# FPGA_ADC_N.net
KiCad netlist of a schematic drawn in Altium Designer
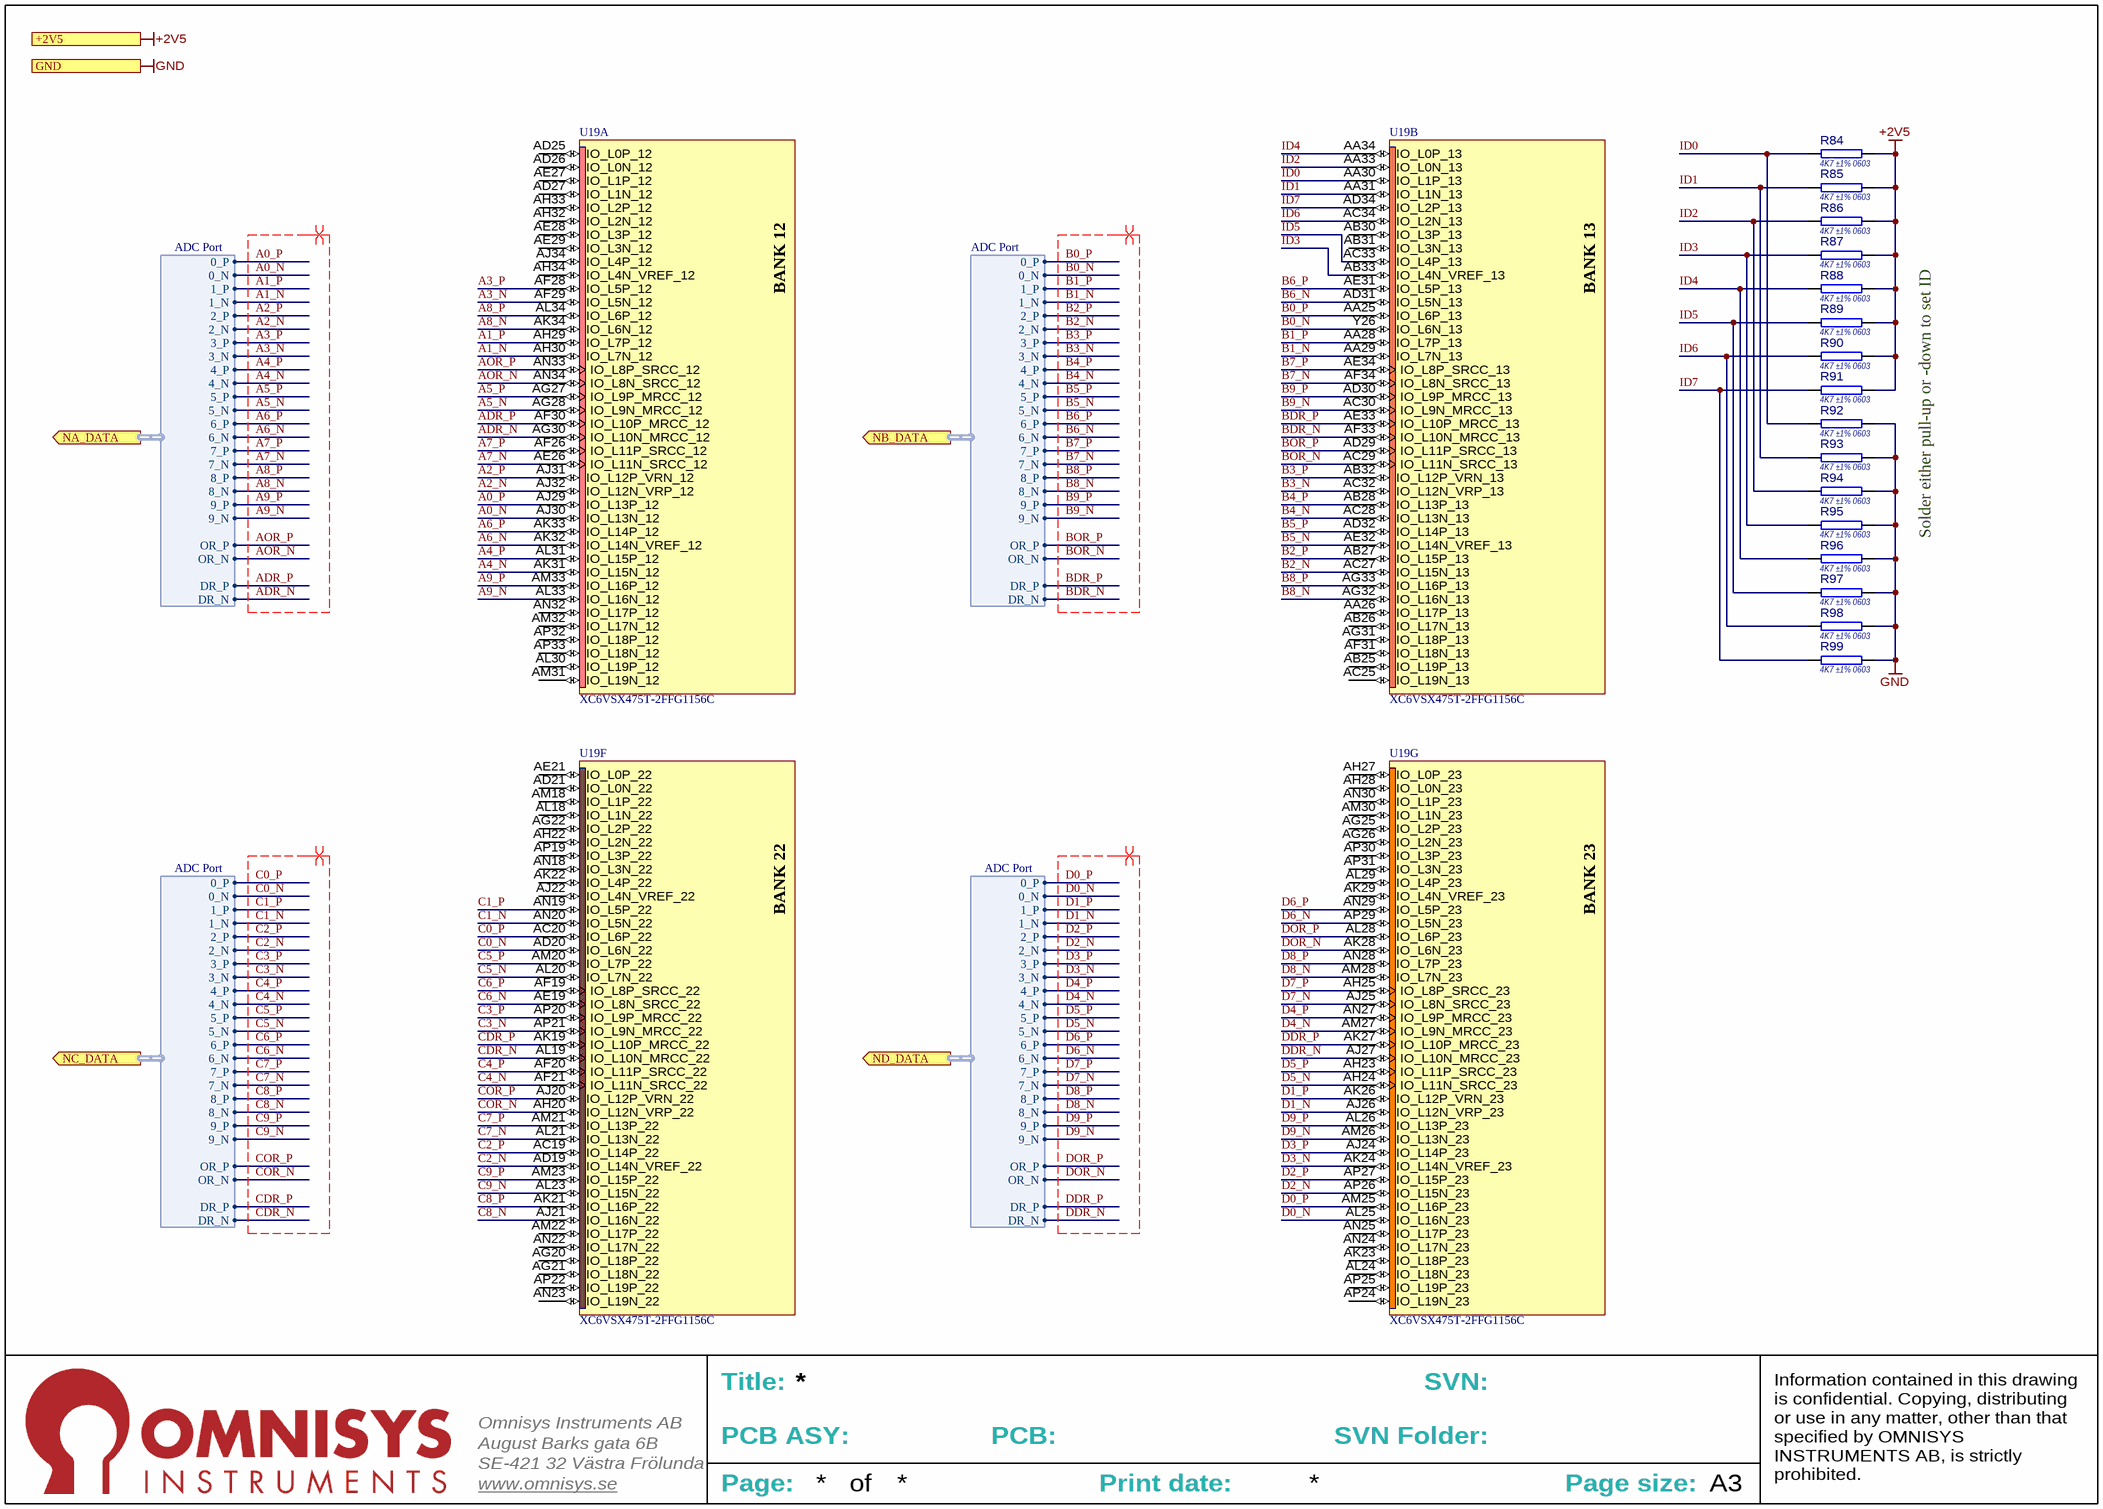
[diagram p0: FPGA_ADC_N.SchDoc]

(export (version "E")
  (design (tool "Eeschema 10.0.6"))
  (components
    (comp (ref "R84")
      (value "4K7 ±1% 0603")
      (footprint "RESC1608N")
      (description "4K7 ±1% ±100 ppm/˚C 0.10W 75V 0603 (1608 metric)")
      (fields (field (name "POWER") "100mW") (field (name "TOLERANCE") "1%"))
      (libsource (lib "Omnisys Vault") (part "RES-2PIN"))
    )
    (comp (ref "R85")
      (value "4K7 ±1% 0603")
      (footprint "RESC1608N")
      (description "4K7 ±1% ±100 ppm/˚C 0.10W 75V 0603 (1608 metric)")
      (fields (field (name "POWER") "100mW") (field (name "TOLERANCE") "1%"))
      (libsource (lib "Omnisys Vault") (part "RES-2PIN"))
    )
    (comp (ref "R86")
      (value "4K7 ±1% 0603")
      (footprint "RESC1608N")
      (description "4K7 ±1% ±100 ppm/˚C 0.10W 75V 0603 (1608 metric)")
      (fields (field (name "POWER") "100mW") (field (name "TOLERANCE") "1%"))
      (libsource (lib "Omnisys Vault") (part "RES-2PIN"))
    )
    (comp (ref "R87")
      (value "4K7 ±1% 0603")
      (footprint "RESC1608N")
      (description "4K7 ±1% ±100 ppm/˚C 0.10W 75V 0603 (1608 metric)")
      (fields (field (name "POWER") "100mW") (field (name "TOLERANCE") "1%"))
      (libsource (lib "Omnisys Vault") (part "RES-2PIN"))
    )
    (comp (ref "R88")
      (value "4K7 ±1% 0603")
      (footprint "RESC1608N")
      (description "4K7 ±1% ±100 ppm/˚C 0.10W 75V 0603 (1608 metric)")
      (fields (field (name "POWER") "100mW") (field (name "TOLERANCE") "1%"))
      (libsource (lib "Omnisys Vault") (part "RES-2PIN"))
    )
    (comp (ref "R89")
      (value "4K7 ±1% 0603")
      (footprint "RESC1608N")
      (description "4K7 ±1% ±100 ppm/˚C 0.10W 75V 0603 (1608 metric)")
      (fields (field (name "POWER") "100mW") (field (name "TOLERANCE") "1%"))
      (libsource (lib "Omnisys Vault") (part "RES-2PIN"))
    )
    (comp (ref "R90")
      (value "4K7 ±1% 0603")
      (footprint "RESC1608N")
      (description "4K7 ±1% ±100 ppm/˚C 0.10W 75V 0603 (1608 metric)")
      (fields (field (name "POWER") "100mW") (field (name "TOLERANCE") "1%"))
      (libsource (lib "Omnisys Vault") (part "RES-2PIN"))
    )
    (comp (ref "R91")
      (value "4K7 ±1% 0603")
      (footprint "RESC1608N")
      (description "4K7 ±1% ±100 ppm/˚C 0.10W 75V 0603 (1608 metric)")
      (fields (field (name "POWER") "100mW") (field (name "TOLERANCE") "1%"))
      (libsource (lib "Omnisys Vault") (part "RES-2PIN"))
    )
    (comp (ref "R92")
      (value "4K7 ±1% 0603")
      (footprint "RESC1608N")
      (description "4K7 ±1% ±100 ppm/˚C 0.10W 75V 0603 (1608 metric)")
      (fields (field (name "POWER") "100mW") (field (name "TOLERANCE") "1%"))
      (libsource (lib "Omnisys Vault") (part "RES-2PIN"))
    )
    (comp (ref "R93")
      (value "4K7 ±1% 0603")
      (footprint "RESC1608N")
      (description "4K7 ±1% ±100 ppm/˚C 0.10W 75V 0603 (1608 metric)")
      (fields (field (name "POWER") "100mW") (field (name "TOLERANCE") "1%"))
      (libsource (lib "Omnisys Vault") (part "RES-2PIN"))
    )
    (comp (ref "R94")
      (value "4K7 ±1% 0603")
      (footprint "RESC1608N")
      (description "4K7 ±1% ±100 ppm/˚C 0.10W 75V 0603 (1608 metric)")
      (fields (field (name "POWER") "100mW") (field (name "TOLERANCE") "1%"))
      (libsource (lib "Omnisys Vault") (part "RES-2PIN"))
    )
    (comp (ref "R95")
      (value "4K7 ±1% 0603")
      (footprint "RESC1608N")
      (description "4K7 ±1% ±100 ppm/˚C 0.10W 75V 0603 (1608 metric)")
      (fields (field (name "POWER") "100mW") (field (name "TOLERANCE") "1%"))
      (libsource (lib "Omnisys Vault") (part "RES-2PIN"))
    )
    (comp (ref "R96")
      (value "4K7 ±1% 0603")
      (footprint "RESC1608N")
      (description "4K7 ±1% ±100 ppm/˚C 0.10W 75V 0603 (1608 metric)")
      (fields (field (name "POWER") "100mW") (field (name "TOLERANCE") "1%"))
      (libsource (lib "Omnisys Vault") (part "RES-2PIN"))
    )
    (comp (ref "R97")
      (value "4K7 ±1% 0603")
      (footprint "RESC1608N")
      (description "4K7 ±1% ±100 ppm/˚C 0.10W 75V 0603 (1608 metric)")
      (fields (field (name "POWER") "100mW") (field (name "TOLERANCE") "1%"))
      (libsource (lib "Omnisys Vault") (part "RES-2PIN"))
    )
    (comp (ref "R98")
      (value "4K7 ±1% 0603")
      (footprint "RESC1608N")
      (description "4K7 ±1% ±100 ppm/˚C 0.10W 75V 0603 (1608 metric)")
      (fields (field (name "POWER") "100mW") (field (name "TOLERANCE") "1%"))
      (libsource (lib "Omnisys Vault") (part "RES-2PIN"))
    )
    (comp (ref "R99")
      (value "4K7 ±1% 0603")
      (footprint "RESC1608N")
      (description "4K7 ±1% ±100 ppm/˚C 0.10W 75V 0603 (1608 metric)")
      (fields (field (name "POWER") "100mW") (field (name "TOLERANCE") "1%"))
      (libsource (lib "Omnisys Vault") (part "RES-2PIN"))
    )
    (comp (ref "U19")
      (value "XC6VSX475T-2FFG1156C")
      (footprint "FFG1156")
      (libsource (lib "Altium Content Vault") (part "FPGA-XVR6-XC6VXXXXXT-GA1156"))
    )
  )
  (nets
    (net (code "3") (name "+2V5") (class "Default")
      (node (ref "R84") (pin "1") (pinfunction "1_1") (pintype "passive"))
      (node (ref "R85") (pin "1") (pinfunction "1_1") (pintype "passive"))
      (node (ref "R86") (pin "1") (pinfunction "1_1") (pintype "passive"))
      (node (ref "R87") (pin "1") (pinfunction "1_1") (pintype "passive"))
      (node (ref "R88") (pin "1") (pinfunction "1_1") (pintype "passive"))
      (node (ref "R89") (pin "1") (pinfunction "1_1") (pintype "passive"))
      (node (ref "R90") (pin "1") (pinfunction "1_1") (pintype "passive"))
      (node (ref "R91") (pin "1") (pinfunction "1_1") (pintype "passive"))
    )
    (net (code "4") (name "/A0_N") (class "Default")
      (node (ref "U19") (pin "AJ30") (pinfunction "IO_L13N_12_AJ30") (pintype "bidirectional"))
    )
    (net (code "5") (name "/A0_P") (class "Default")
      (node (ref "U19") (pin "AJ29") (pinfunction "IO_L13P_12_AJ29") (pintype "bidirectional"))
    )
    (net (code "6") (name "/A1_N") (class "Default")
      (node (ref "U19") (pin "AH30") (pinfunction "IO_L7N_12_AH30") (pintype "bidirectional"))
    )
    (net (code "7") (name "/A1_P") (class "Default")
      (node (ref "U19") (pin "AH29") (pinfunction "IO_L7P_12_AH29") (pintype "bidirectional"))
    )
    (net (code "8") (name "/A2_N") (class "Default")
      (node (ref "U19") (pin "AJ32") (pinfunction "IO_L12N_VRP_12_AJ32") (pintype "bidirectional"))
    )
    (net (code "9") (name "/A2_P") (class "Default")
      (node (ref "U19") (pin "AJ31") (pinfunction "IO_L12P_VRN_12_AJ31") (pintype "bidirectional"))
    )
    (net (code "10") (name "/A3_N") (class "Default")
      (node (ref "U19") (pin "AF29") (pinfunction "IO_L5N_12_AF29") (pintype "bidirectional"))
    )
    (net (code "11") (name "/A3_P") (class "Default")
      (node (ref "U19") (pin "AF28") (pinfunction "IO_L5P_12_AF28") (pintype "bidirectional"))
    )
    (net (code "12") (name "/A4_N") (class "Default")
      (node (ref "U19") (pin "AK31") (pinfunction "IO_L15N_12_AK31") (pintype "bidirectional"))
    )
    (net (code "13") (name "/A4_P") (class "Default")
      (node (ref "U19") (pin "AL31") (pinfunction "IO_L15P_12_AL31") (pintype "bidirectional"))
    )
    (net (code "14") (name "/A5_N") (class "Default")
      (node (ref "U19") (pin "AG28") (pinfunction "IO_L9N_MRCC_12_AG28") (pintype "bidirectional"))
    )
    (net (code "15") (name "/A5_P") (class "Default")
      (node (ref "U19") (pin "AG27") (pinfunction "IO_L9P_MRCC_12_AG27") (pintype "bidirectional"))
    )
    (net (code "16") (name "/A6_N") (class "Default")
      (node (ref "U19") (pin "AK32") (pinfunction "IO_L14N_VREF_12_AK32") (pintype "bidirectional"))
    )
    (net (code "17") (name "/A6_P") (class "Default")
      (node (ref "U19") (pin "AK33") (pinfunction "IO_L14P_12_AK33") (pintype "bidirectional"))
    )
    (net (code "18") (name "/A7_N") (class "Default")
      (node (ref "U19") (pin "AE26") (pinfunction "IO_L11N_SRCC_12_AE26") (pintype "bidirectional"))
    )
    (net (code "19") (name "/A7_P") (class "Default")
      (node (ref "U19") (pin "AF26") (pinfunction "IO_L11P_SRCC_12_AF26") (pintype "bidirectional"))
    )
    (net (code "20") (name "/A8_N") (class "Default")
      (node (ref "U19") (pin "AK34") (pinfunction "IO_L6N_12_AK34") (pintype "bidirectional"))
    )
    (net (code "21") (name "/A8_P") (class "Default")
      (node (ref "U19") (pin "AL34") (pinfunction "IO_L6P_12_AL34") (pintype "bidirectional"))
    )
    (net (code "22") (name "/A9_N") (class "Default")
      (node (ref "U19") (pin "AL33") (pinfunction "IO_L16N_12_AL33") (pintype "bidirectional"))
    )
    (net (code "23") (name "/A9_P") (class "Default")
      (node (ref "U19") (pin "AM33") (pinfunction "IO_L16P_12_AM33") (pintype "bidirectional"))
    )
    (net (code "24") (name "/ADR_N") (class "Default")
      (node (ref "U19") (pin "AG30") (pinfunction "IO_L10N_MRCC_12_AG30") (pintype "bidirectional"))
    )
    (net (code "25") (name "/ADR_P") (class "Default")
      (node (ref "U19") (pin "AF30") (pinfunction "IO_L10P_MRCC_12_AF30") (pintype "bidirectional"))
    )
    (net (code "26") (name "/AOR_N") (class "Default")
      (node (ref "U19") (pin "AN34") (pinfunction "IO_L8N_SRCC_12_AN34") (pintype "bidirectional"))
    )
    (net (code "27") (name "/AOR_P") (class "Default")
      (node (ref "U19") (pin "AN33") (pinfunction "IO_L8P_SRCC_12_AN33") (pintype "bidirectional"))
    )
    (net (code "28") (name "/B0_N") (class "Default")
      (node (ref "U19") (pin "Y26") (pinfunction "IO_L6N_13_Y26") (pintype "bidirectional"))
    )
    (net (code "29") (name "/B0_P") (class "Default")
      (node (ref "U19") (pin "AA25") (pinfunction "IO_L6P_13_AA25") (pintype "bidirectional"))
    )
    (net (code "30") (name "/B1_N") (class "Default")
      (node (ref "U19") (pin "AA29") (pinfunction "IO_L7N_13_AA29") (pintype "bidirectional"))
    )
    (net (code "31") (name "/B1_P") (class "Default")
      (node (ref "U19") (pin "AA28") (pinfunction "IO_L7P_13_AA28") (pintype "bidirectional"))
    )
    (net (code "32") (name "/B2_N") (class "Default")
      (node (ref "U19") (pin "AC27") (pinfunction "IO_L15N_13_AC27") (pintype "bidirectional"))
    )
    (net (code "33") (name "/B2_P") (class "Default")
      (node (ref "U19") (pin "AB27") (pinfunction "IO_L15P_13_AB27") (pintype "bidirectional"))
    )
    (net (code "34") (name "/B3_N") (class "Default")
      (node (ref "U19") (pin "AC32") (pinfunction "IO_L12N_VRP_13_AC32") (pintype "bidirectional"))
    )
    (net (code "35") (name "/B3_P") (class "Default")
      (node (ref "U19") (pin "AB32") (pinfunction "IO_L12P_VRN_13_AB32") (pintype "bidirectional"))
    )
    (net (code "36") (name "/B4_N") (class "Default")
      (node (ref "U19") (pin "AC28") (pinfunction "IO_L13N_13_AC28") (pintype "bidirectional"))
    )
    (net (code "37") (name "/B4_P") (class "Default")
      (node (ref "U19") (pin "AB28") (pinfunction "IO_L13P_13_AB28") (pintype "bidirectional"))
    )
    (net (code "38") (name "/B5_N") (class "Default")
      (node (ref "U19") (pin "AE32") (pinfunction "IO_L14N_VREF_13_AE32") (pintype "bidirectional"))
    )
    (net (code "39") (name "/B5_P") (class "Default")
      (node (ref "U19") (pin "AD32") (pinfunction "IO_L14P_13_AD32") (pintype "bidirectional"))
    )
    (net (code "40") (name "/B6_N") (class "Default")
      (node (ref "U19") (pin "AD31") (pinfunction "IO_L5N_13_AD31") (pintype "bidirectional"))
    )
    (net (code "41") (name "/B6_P") (class "Default")
      (node (ref "U19") (pin "AE31") (pinfunction "IO_L5P_13_AE31") (pintype "bidirectional"))
    )
    (net (code "42") (name "/B7_N") (class "Default")
      (node (ref "U19") (pin "AF34") (pinfunction "IO_L8N_SRCC_13_AF34") (pintype "bidirectional"))
    )
    (net (code "43") (name "/B7_P") (class "Default")
      (node (ref "U19") (pin "AE34") (pinfunction "IO_L8P_SRCC_13_AE34") (pintype "bidirectional"))
    )
    (net (code "44") (name "/B8_N") (class "Default")
      (node (ref "U19") (pin "AG32") (pinfunction "IO_L16N_13_AG32") (pintype "bidirectional"))
    )
    (net (code "45") (name "/B8_P") (class "Default")
      (node (ref "U19") (pin "AG33") (pinfunction "IO_L16P_13_AG33") (pintype "bidirectional"))
    )
    (net (code "46") (name "/B9_N") (class "Default")
      (node (ref "U19") (pin "AC30") (pinfunction "IO_L9N_MRCC_13_AC30") (pintype "bidirectional"))
    )
    (net (code "47") (name "/B9_P") (class "Default")
      (node (ref "U19") (pin "AD30") (pinfunction "IO_L9P_MRCC_13_AD30") (pintype "bidirectional"))
    )
    (net (code "48") (name "/BDR_N") (class "Default")
      (node (ref "U19") (pin "AF33") (pinfunction "IO_L10N_MRCC_13_AF33") (pintype "bidirectional"))
    )
    (net (code "49") (name "/BDR_P") (class "Default")
      (node (ref "U19") (pin "AE33") (pinfunction "IO_L10P_MRCC_13_AE33") (pintype "bidirectional"))
    )
    (net (code "50") (name "/BOR_N") (class "Default")
      (node (ref "U19") (pin "AC29") (pinfunction "IO_L11N_SRCC_13_AC29") (pintype "bidirectional"))
    )
    (net (code "51") (name "/BOR_P") (class "Default")
      (node (ref "U19") (pin "AD29") (pinfunction "IO_L11P_SRCC_13_AD29") (pintype "bidirectional"))
    )
    (net (code "52") (name "/C0_N") (class "Default")
      (node (ref "U19") (pin "AD20") (pinfunction "IO_L6N_22_AD20") (pintype "bidirectional"))
    )
    (net (code "53") (name "/C0_P") (class "Default")
      (node (ref "U19") (pin "AC20") (pinfunction "IO_L6P_22_AC20") (pintype "bidirectional"))
    )
    (net (code "54") (name "/C1_N") (class "Default")
      (node (ref "U19") (pin "AN20") (pinfunction "IO_L5N_22_AN20") (pintype "bidirectional"))
    )
    (net (code "55") (name "/C1_P") (class "Default")
      (node (ref "U19") (pin "AN19") (pinfunction "IO_L5P_22_AN19") (pintype "bidirectional"))
    )
    (net (code "56") (name "/C2_N") (class "Default")
      (node (ref "U19") (pin "AD19") (pinfunction "IO_L14N_VREF_22_AD19") (pintype "bidirectional"))
    )
    (net (code "57") (name "/C2_P") (class "Default")
      (node (ref "U19") (pin "AC19") (pinfunction "IO_L14P_22_AC19") (pintype "bidirectional"))
    )
    (net (code "58") (name "/C3_N") (class "Default")
      (node (ref "U19") (pin "AP21") (pinfunction "IO_L9N_MRCC_22_AP21") (pintype "bidirectional"))
    )
    (net (code "59") (name "/C3_P") (class "Default")
      (node (ref "U19") (pin "AP20") (pinfunction "IO_L9P_MRCC_22_AP20") (pintype "bidirectional"))
    )
    (net (code "60") (name "/C4_N") (class "Default")
      (node (ref "U19") (pin "AF21") (pinfunction "IO_L11N_SRCC_22_AF21") (pintype "bidirectional"))
    )
    (net (code "61") (name "/C4_P") (class "Default")
      (node (ref "U19") (pin "AF20") (pinfunction "IO_L11P_SRCC_22_AF20") (pintype "bidirectional"))
    )
    (net (code "62") (name "/C5_N") (class "Default")
      (node (ref "U19") (pin "AL20") (pinfunction "IO_L7N_22_AL20") (pintype "bidirectional"))
    )
    (net (code "63") (name "/C5_P") (class "Default")
      (node (ref "U19") (pin "AM20") (pinfunction "IO_L7P_22_AM20") (pintype "bidirectional"))
    )
    (net (code "64") (name "/C6_N") (class "Default")
      (node (ref "U19") (pin "AE19") (pinfunction "IO_L8N_SRCC_22_AE19") (pintype "bidirectional"))
    )
    (net (code "65") (name "/C6_P") (class "Default")
      (node (ref "U19") (pin "AF19") (pinfunction "IO_L8P_SRCC_22_AF19") (pintype "bidirectional"))
    )
    (net (code "66") (name "/C7_N") (class "Default")
      (node (ref "U19") (pin "AL21") (pinfunction "IO_L13N_22_AL21") (pintype "bidirectional"))
    )
    (net (code "67") (name "/C7_P") (class "Default")
      (node (ref "U19") (pin "AM21") (pinfunction "IO_L13P_22_AM21") (pintype "bidirectional"))
    )
    (net (code "68") (name "/C8_N") (class "Default")
      (node (ref "U19") (pin "AJ21") (pinfunction "IO_L16N_22_AJ21") (pintype "bidirectional"))
    )
    (net (code "69") (name "/C8_P") (class "Default")
      (node (ref "U19") (pin "AK21") (pinfunction "IO_L16P_22_AK21") (pintype "bidirectional"))
    )
    (net (code "70") (name "/C9_N") (class "Default")
      (node (ref "U19") (pin "AL23") (pinfunction "IO_L15N_22_AL23") (pintype "bidirectional"))
    )
    (net (code "71") (name "/C9_P") (class "Default")
      (node (ref "U19") (pin "AM23") (pinfunction "IO_L15P_22_AM23") (pintype "bidirectional"))
    )
    (net (code "72") (name "/CDR_N") (class "Default")
      (node (ref "U19") (pin "AL19") (pinfunction "IO_L10N_MRCC_22_AL19") (pintype "bidirectional"))
    )
    (net (code "73") (name "/CDR_P") (class "Default")
      (node (ref "U19") (pin "AK19") (pinfunction "IO_L10P_MRCC_22_AK19") (pintype "bidirectional"))
    )
    (net (code "74") (name "/COR_N") (class "Default")
      (node (ref "U19") (pin "AH20") (pinfunction "IO_L12N_VRP_22_AH20") (pintype "bidirectional"))
    )
    (net (code "75") (name "/COR_P") (class "Default")
      (node (ref "U19") (pin "AJ20") (pinfunction "IO_L12P_VRN_22_AJ20") (pintype "bidirectional"))
    )
    (net (code "76") (name "/D0_N") (class "Default")
      (node (ref "U19") (pin "AL25") (pinfunction "IO_L16N_23_AL25") (pintype "bidirectional"))
    )
    (net (code "77") (name "/D0_P") (class "Default")
      (node (ref "U19") (pin "AM25") (pinfunction "IO_L16P_23_AM25") (pintype "bidirectional"))
    )
    (net (code "78") (name "/D1_N") (class "Default")
      (node (ref "U19") (pin "AJ26") (pinfunction "IO_L12N_VRP_23_AJ26") (pintype "bidirectional"))
    )
    (net (code "79") (name "/D1_P") (class "Default")
      (node (ref "U19") (pin "AK26") (pinfunction "IO_L12P_VRN_23_AK26") (pintype "bidirectional"))
    )
    (net (code "80") (name "/D2_N") (class "Default")
      (node (ref "U19") (pin "AP26") (pinfunction "IO_L15N_23_AP26") (pintype "bidirectional"))
    )
    (net (code "81") (name "/D2_P") (class "Default")
      (node (ref "U19") (pin "AP27") (pinfunction "IO_L15P_23_AP27") (pintype "bidirectional"))
    )
    (net (code "82") (name "/D3_N") (class "Default")
      (node (ref "U19") (pin "AK24") (pinfunction "IO_L14N_VREF_23_AK24") (pintype "bidirectional"))
    )
    (net (code "83") (name "/D3_P") (class "Default")
      (node (ref "U19") (pin "AJ24") (pinfunction "IO_L14P_23_AJ24") (pintype "bidirectional"))
    )
    (net (code "84") (name "/D4_N") (class "Default")
      (node (ref "U19") (pin "AM27") (pinfunction "IO_L9N_MRCC_23_AM27") (pintype "bidirectional"))
    )
    (net (code "85") (name "/D4_P") (class "Default")
      (node (ref "U19") (pin "AN27") (pinfunction "IO_L9P_MRCC_23_AN27") (pintype "bidirectional"))
    )
    (net (code "86") (name "/D5_N") (class "Default")
      (node (ref "U19") (pin "AH24") (pinfunction "IO_L11N_SRCC_23_AH24") (pintype "bidirectional"))
    )
    (net (code "87") (name "/D5_P") (class "Default")
      (node (ref "U19") (pin "AH23") (pinfunction "IO_L11P_SRCC_23_AH23") (pintype "bidirectional"))
    )
    (net (code "88") (name "/D6_N") (class "Default")
      (node (ref "U19") (pin "AP29") (pinfunction "IO_L5N_23_AP29") (pintype "bidirectional"))
    )
    (net (code "89") (name "/D6_P") (class "Default")
      (node (ref "U19") (pin "AN29") (pinfunction "IO_L5P_23_AN29") (pintype "bidirectional"))
    )
    (net (code "90") (name "/D7_N") (class "Default")
      (node (ref "U19") (pin "AJ25") (pinfunction "IO_L8N_SRCC_23_AJ25") (pintype "bidirectional"))
    )
    (net (code "91") (name "/D7_P") (class "Default")
      (node (ref "U19") (pin "AH25") (pinfunction "IO_L8P_SRCC_23_AH25") (pintype "bidirectional"))
    )
    (net (code "92") (name "/D8_N") (class "Default")
      (node (ref "U19") (pin "AM28") (pinfunction "IO_L7N_23_AM28") (pintype "bidirectional"))
    )
    (net (code "93") (name "/D8_P") (class "Default")
      (node (ref "U19") (pin "AN28") (pinfunction "IO_L7P_23_AN28") (pintype "bidirectional"))
    )
    (net (code "94") (name "/D9_N") (class "Default")
      (node (ref "U19") (pin "AM26") (pinfunction "IO_L13N_23_AM26") (pintype "bidirectional"))
    )
    (net (code "95") (name "/D9_P") (class "Default")
      (node (ref "U19") (pin "AL26") (pinfunction "IO_L13P_23_AL26") (pintype "bidirectional"))
    )
    (net (code "96") (name "/DDR_N") (class "Default")
      (node (ref "U19") (pin "AJ27") (pinfunction "IO_L10N_MRCC_23_AJ27") (pintype "bidirectional"))
    )
    (net (code "97") (name "/DDR_P") (class "Default")
      (node (ref "U19") (pin "AK27") (pinfunction "IO_L10P_MRCC_23_AK27") (pintype "bidirectional"))
    )
    (net (code "98") (name "/DOR_N") (class "Default")
      (node (ref "U19") (pin "AK28") (pinfunction "IO_L6N_23_AK28") (pintype "bidirectional"))
    )
    (net (code "99") (name "/DOR_P") (class "Default")
      (node (ref "U19") (pin "AL28") (pinfunction "IO_L6P_23_AL28") (pintype "bidirectional"))
    )
    (net (code "100") (name "/ID0") (class "Default")
      (node (ref "R84") (pin "2") (pinfunction "2_2") (pintype "passive"))
      (node (ref "R92") (pin "2") (pinfunction "2_2") (pintype "passive"))
      (node (ref "U19") (pin "AA30") (pinfunction "IO_L1P_13_AA30") (pintype "bidirectional"))
    )
    (net (code "101") (name "/ID1") (class "Default")
      (node (ref "R85") (pin "2") (pinfunction "2_2") (pintype "passive"))
      (node (ref "R93") (pin "2") (pinfunction "2_2") (pintype "passive"))
      (node (ref "U19") (pin "AA31") (pinfunction "IO_L1N_13_AA31") (pintype "bidirectional"))
    )
    (net (code "102") (name "/ID2") (class "Default")
      (node (ref "R86") (pin "2") (pinfunction "2_2") (pintype "passive"))
      (node (ref "R94") (pin "2") (pinfunction "2_2") (pintype "passive"))
      (node (ref "U19") (pin "AA33") (pinfunction "IO_L0N_13_AA33") (pintype "bidirectional"))
    )
    (net (code "103") (name "/ID3") (class "Default")
      (node (ref "R87") (pin "2") (pinfunction "2_2") (pintype "passive"))
      (node (ref "R95") (pin "2") (pinfunction "2_2") (pintype "passive"))
      (node (ref "U19") (pin "AB33") (pinfunction "IO_L4N_VREF_13_AB33") (pintype "bidirectional"))
    )
    (net (code "104") (name "/ID4") (class "Default")
      (node (ref "R88") (pin "2") (pinfunction "2_2") (pintype "passive"))
      (node (ref "R96") (pin "2") (pinfunction "2_2") (pintype "passive"))
      (node (ref "U19") (pin "AA34") (pinfunction "IO_L0P_13_AA34") (pintype "bidirectional"))
    )
    (net (code "105") (name "/ID5") (class "Default")
      (node (ref "R89") (pin "2") (pinfunction "2_2") (pintype "passive"))
      (node (ref "R97") (pin "2") (pinfunction "2_2") (pintype "passive"))
      (node (ref "U19") (pin "AC33") (pinfunction "IO_L4P_13_AC33") (pintype "bidirectional"))
    )
    (net (code "106") (name "/ID6") (class "Default")
      (node (ref "R90") (pin "2") (pinfunction "2_2") (pintype "passive"))
      (node (ref "R98") (pin "2") (pinfunction "2_2") (pintype "passive"))
      (node (ref "U19") (pin "AC34") (pinfunction "IO_L2N_13_AC34") (pintype "bidirectional"))
    )
    (net (code "107") (name "/ID7") (class "Default")
      (node (ref "R91") (pin "2") (pinfunction "2_2") (pintype "passive"))
      (node (ref "R99") (pin "2") (pinfunction "2_2") (pintype "passive"))
      (node (ref "U19") (pin "AD34") (pinfunction "IO_L2P_13_AD34") (pintype "bidirectional"))
    )
    (net (code "109") (name "GND") (class "Default")
      (node (ref "R92") (pin "1") (pinfunction "1_1") (pintype "passive"))
      (node (ref "R93") (pin "1") (pinfunction "1_1") (pintype "passive"))
      (node (ref "R94") (pin "1") (pinfunction "1_1") (pintype "passive"))
      (node (ref "R95") (pin "1") (pinfunction "1_1") (pintype "passive"))
      (node (ref "R96") (pin "1") (pinfunction "1_1") (pintype "passive"))
      (node (ref "R97") (pin "1") (pinfunction "1_1") (pintype "passive"))
      (node (ref "R98") (pin "1") (pinfunction "1_1") (pintype "passive"))
      (node (ref "R99") (pin "1") (pinfunction "1_1") (pintype "passive"))
    )
    (net (code "110") (name "unconnected-(U19A-IO_L0N_12-PadAD26)") (class "Default")
      (node (ref "U19") (pin "AD26") (pinfunction "IO_L0N_12_AD26") (pintype "bidirectional"))
    )
    (net (code "111") (name "unconnected-(U19A-IO_L0P_12-PadAD25)") (class "Default")
      (node (ref "U19") (pin "AD25") (pinfunction "IO_L0P_12_AD25") (pintype "bidirectional"))
    )
    (net (code "112") (name "unconnected-(U19A-IO_L1N_12-PadAD27)") (class "Default")
      (node (ref "U19") (pin "AD27") (pinfunction "IO_L1N_12_AD27") (pintype "bidirectional"))
    )
    (net (code "113") (name "unconnected-(U19A-IO_L1P_12-PadAE27)") (class "Default")
      (node (ref "U19") (pin "AE27") (pinfunction "IO_L1P_12_AE27") (pintype "bidirectional"))
    )
    (net (code "114") (name "unconnected-(U19A-IO_L2N_12-PadAH32)") (class "Default")
      (node (ref "U19") (pin "AH32") (pinfunction "IO_L2N_12_AH32") (pintype "bidirectional"))
    )
    (net (code "115") (name "unconnected-(U19A-IO_L2P_12-PadAH33)") (class "Default")
      (node (ref "U19") (pin "AH33") (pinfunction "IO_L2P_12_AH33") (pintype "bidirectional"))
    )
    (net (code "116") (name "unconnected-(U19A-IO_L3N_12-PadAE29)") (class "Default")
      (node (ref "U19") (pin "AE29") (pinfunction "IO_L3N_12_AE29") (pintype "bidirectional"))
    )
    (net (code "117") (name "unconnected-(U19A-IO_L3P_12-PadAE28)") (class "Default")
      (node (ref "U19") (pin "AE28") (pinfunction "IO_L3P_12_AE28") (pintype "bidirectional"))
    )
    (net (code "118") (name "unconnected-(U19A-IO_L4N_VREF_12-PadAH34)") (class "Default")
      (node (ref "U19") (pin "AH34") (pinfunction "IO_L4N_VREF_12_AH34") (pintype "bidirectional"))
    )
    (net (code "119") (name "unconnected-(U19A-IO_L4P_12-PadAJ34)") (class "Default")
      (node (ref "U19") (pin "AJ34") (pinfunction "IO_L4P_12_AJ34") (pintype "bidirectional"))
    )
    (net (code "120") (name "unconnected-(U19A-IO_L17N_12-PadAM32)") (class "Default")
      (node (ref "U19") (pin "AM32") (pinfunction "IO_L17N_12_AM32") (pintype "bidirectional"))
    )
    (net (code "121") (name "unconnected-(U19A-IO_L17P_12-PadAN32)") (class "Default")
      (node (ref "U19") (pin "AN32") (pinfunction "IO_L17P_12_AN32") (pintype "bidirectional"))
    )
    (net (code "122") (name "unconnected-(U19A-IO_L18N_12-PadAP33)") (class "Default")
      (node (ref "U19") (pin "AP33") (pinfunction "IO_L18N_12_AP33") (pintype "bidirectional"))
    )
    (net (code "123") (name "unconnected-(U19A-IO_L18P_12-PadAP32)") (class "Default")
      (node (ref "U19") (pin "AP32") (pinfunction "IO_L18P_12_AP32") (pintype "bidirectional"))
    )
    (net (code "124") (name "unconnected-(U19A-IO_L19N_12-PadAM31)") (class "Default")
      (node (ref "U19") (pin "AM31") (pinfunction "IO_L19N_12_AM31") (pintype "bidirectional"))
    )
    (net (code "125") (name "unconnected-(U19A-IO_L19P_12-PadAL30)") (class "Default")
      (node (ref "U19") (pin "AL30") (pinfunction "IO_L19P_12_AL30") (pintype "bidirectional"))
    )
    (net (code "126") (name "unconnected-(U19B-IO_L3N_13-PadAB31)") (class "Default")
      (node (ref "U19") (pin "AB31") (pinfunction "IO_L3N_13_AB31") (pintype "bidirectional"))
    )
    (net (code "127") (name "unconnected-(U19B-IO_L3P_13-PadAB30)") (class "Default")
      (node (ref "U19") (pin "AB30") (pinfunction "IO_L3P_13_AB30") (pintype "bidirectional"))
    )
    (net (code "128") (name "unconnected-(U19B-IO_L17N_13-PadAB26)") (class "Default")
      (node (ref "U19") (pin "AB26") (pinfunction "IO_L17N_13_AB26") (pintype "bidirectional"))
    )
    (net (code "129") (name "unconnected-(U19B-IO_L17P_13-PadAA26)") (class "Default")
      (node (ref "U19") (pin "AA26") (pinfunction "IO_L17P_13_AA26") (pintype "bidirectional"))
    )
    (net (code "130") (name "unconnected-(U19B-IO_L18N_13-PadAF31)") (class "Default")
      (node (ref "U19") (pin "AF31") (pinfunction "IO_L18N_13_AF31") (pintype "bidirectional"))
    )
    (net (code "131") (name "unconnected-(U19B-IO_L18P_13-PadAG31)") (class "Default")
      (node (ref "U19") (pin "AG31") (pinfunction "IO_L18P_13_AG31") (pintype "bidirectional"))
    )
    (net (code "132") (name "unconnected-(U19B-IO_L19N_13-PadAC25)") (class "Default")
      (node (ref "U19") (pin "AC25") (pinfunction "IO_L19N_13_AC25") (pintype "bidirectional"))
    )
    (net (code "133") (name "unconnected-(U19B-IO_L19P_13-PadAB25)") (class "Default")
      (node (ref "U19") (pin "AB25") (pinfunction "IO_L19P_13_AB25") (pintype "bidirectional"))
    )
    (net (code "134") (name "unconnected-(U19F-IO_L0N_22-PadAD21)") (class "Default")
      (node (ref "U19") (pin "AD21") (pinfunction "IO_L0N_22_AD21") (pintype "bidirectional"))
    )
    (net (code "135") (name "unconnected-(U19F-IO_L0P_22-PadAE21)") (class "Default")
      (node (ref "U19") (pin "AE21") (pinfunction "IO_L0P_22_AE21") (pintype "bidirectional"))
    )
    (net (code "136") (name "unconnected-(U19F-IO_L1N_22-PadAL18)") (class "Default")
      (node (ref "U19") (pin "AL18") (pinfunction "IO_L1N_22_AL18") (pintype "bidirectional"))
    )
    (net (code "137") (name "unconnected-(U19F-IO_L1P_22-PadAM18)") (class "Default")
      (node (ref "U19") (pin "AM18") (pinfunction "IO_L1P_22_AM18") (pintype "bidirectional"))
    )
    (net (code "138") (name "unconnected-(U19F-IO_L2N_22-PadAH22)") (class "Default")
      (node (ref "U19") (pin "AH22") (pinfunction "IO_L2N_22_AH22") (pintype "bidirectional"))
    )
    (net (code "139") (name "unconnected-(U19F-IO_L2P_22-PadAG22)") (class "Default")
      (node (ref "U19") (pin "AG22") (pinfunction "IO_L2P_22_AG22") (pintype "bidirectional"))
    )
    (net (code "140") (name "unconnected-(U19F-IO_L3N_22-PadAN18)") (class "Default")
      (node (ref "U19") (pin "AN18") (pinfunction "IO_L3N_22_AN18") (pintype "bidirectional"))
    )
    (net (code "141") (name "unconnected-(U19F-IO_L3P_22-PadAP19)") (class "Default")
      (node (ref "U19") (pin "AP19") (pinfunction "IO_L3P_22_AP19") (pintype "bidirectional"))
    )
    (net (code "142") (name "unconnected-(U19F-IO_L4N_VREF_22-PadAJ22)") (class "Default")
      (node (ref "U19") (pin "AJ22") (pinfunction "IO_L4N_VREF_22_AJ22") (pintype "bidirectional"))
    )
    (net (code "143") (name "unconnected-(U19F-IO_L4P_22-PadAK22)") (class "Default")
      (node (ref "U19") (pin "AK22") (pinfunction "IO_L4P_22_AK22") (pintype "bidirectional"))
    )
    (net (code "144") (name "unconnected-(U19F-IO_L17N_22-PadAN22)") (class "Default")
      (node (ref "U19") (pin "AN22") (pinfunction "IO_L17N_22_AN22") (pintype "bidirectional"))
    )
    (net (code "145") (name "unconnected-(U19F-IO_L17P_22-PadAM22)") (class "Default")
      (node (ref "U19") (pin "AM22") (pinfunction "IO_L17P_22_AM22") (pintype "bidirectional"))
    )
    (net (code "146") (name "unconnected-(U19F-IO_L18N_22-PadAG21)") (class "Default")
      (node (ref "U19") (pin "AG21") (pinfunction "IO_L18N_22_AG21") (pintype "bidirectional"))
    )
    (net (code "147") (name "unconnected-(U19F-IO_L18P_22-PadAG20)") (class "Default")
      (node (ref "U19") (pin "AG20") (pinfunction "IO_L18P_22_AG20") (pintype "bidirectional"))
    )
    (net (code "148") (name "unconnected-(U19F-IO_L19N_22-PadAN23)") (class "Default")
      (node (ref "U19") (pin "AN23") (pinfunction "IO_L19N_22_AN23") (pintype "bidirectional"))
    )
    (net (code "149") (name "unconnected-(U19F-IO_L19P_22-PadAP22)") (class "Default")
      (node (ref "U19") (pin "AP22") (pinfunction "IO_L19P_22_AP22") (pintype "bidirectional"))
    )
    (net (code "150") (name "unconnected-(U19G-IO_L0N_23-PadAH28)") (class "Default")
      (node (ref "U19") (pin "AH28") (pinfunction "IO_L0N_23_AH28") (pintype "bidirectional"))
    )
    (net (code "151") (name "unconnected-(U19G-IO_L0P_23-PadAH27)") (class "Default")
      (node (ref "U19") (pin "AH27") (pinfunction "IO_L0P_23_AH27") (pintype "bidirectional"))
    )
    (net (code "152") (name "unconnected-(U19G-IO_L1N_23-PadAM30)") (class "Default")
      (node (ref "U19") (pin "AM30") (pinfunction "IO_L1N_23_AM30") (pintype "bidirectional"))
    )
    (net (code "153") (name "unconnected-(U19G-IO_L1P_23-PadAN30)") (class "Default")
      (node (ref "U19") (pin "AN30") (pinfunction "IO_L1P_23_AN30") (pintype "bidirectional"))
    )
    (net (code "154") (name "unconnected-(U19G-IO_L2N_23-PadAG26)") (class "Default")
      (node (ref "U19") (pin "AG26") (pinfunction "IO_L2N_23_AG26") (pintype "bidirectional"))
    )
    (net (code "155") (name "unconnected-(U19G-IO_L2P_23-PadAG25)") (class "Default")
      (node (ref "U19") (pin "AG25") (pinfunction "IO_L2P_23_AG25") (pintype "bidirectional"))
    )
    (net (code "156") (name "unconnected-(U19G-IO_L3N_23-PadAP31)") (class "Default")
      (node (ref "U19") (pin "AP31") (pinfunction "IO_L3N_23_AP31") (pintype "bidirectional"))
    )
    (net (code "157") (name "unconnected-(U19G-IO_L3P_23-PadAP30)") (class "Default")
      (node (ref "U19") (pin "AP30") (pinfunction "IO_L3P_23_AP30") (pintype "bidirectional"))
    )
    (net (code "158") (name "unconnected-(U19G-IO_L4N_VREF_23-PadAK29)") (class "Default")
      (node (ref "U19") (pin "AK29") (pinfunction "IO_L4N_VREF_23_AK29") (pintype "bidirectional"))
    )
    (net (code "159") (name "unconnected-(U19G-IO_L4P_23-PadAL29)") (class "Default")
      (node (ref "U19") (pin "AL29") (pinfunction "IO_L4P_23_AL29") (pintype "bidirectional"))
    )
    (net (code "160") (name "unconnected-(U19G-IO_L17N_23-PadAN24)") (class "Default")
      (node (ref "U19") (pin "AN24") (pinfunction "IO_L17N_23_AN24") (pintype "bidirectional"))
    )
    (net (code "161") (name "unconnected-(U19G-IO_L17P_23-PadAN25)") (class "Default")
      (node (ref "U19") (pin "AN25") (pinfunction "IO_L17P_23_AN25") (pintype "bidirectional"))
    )
    (net (code "162") (name "unconnected-(U19G-IO_L18N_23-PadAL24)") (class "Default")
      (node (ref "U19") (pin "AL24") (pinfunction "IO_L18N_23_AL24") (pintype "bidirectional"))
    )
    (net (code "163") (name "unconnected-(U19G-IO_L18P_23-PadAK23)") (class "Default")
      (node (ref "U19") (pin "AK23") (pinfunction "IO_L18P_23_AK23") (pintype "bidirectional"))
    )
    (net (code "164") (name "unconnected-(U19G-IO_L19N_23-PadAP24)") (class "Default")
      (node (ref "U19") (pin "AP24") (pinfunction "IO_L19N_23_AP24") (pintype "bidirectional"))
    )
    (net (code "165") (name "unconnected-(U19G-IO_L19P_23-PadAP25)") (class "Default")
      (node (ref "U19") (pin "AP25") (pinfunction "IO_L19P_23_AP25") (pintype "bidirectional"))
    )
  )
)
